# PTGSCH1.net
KiCad netlist of a schematic drawn in EAGLE
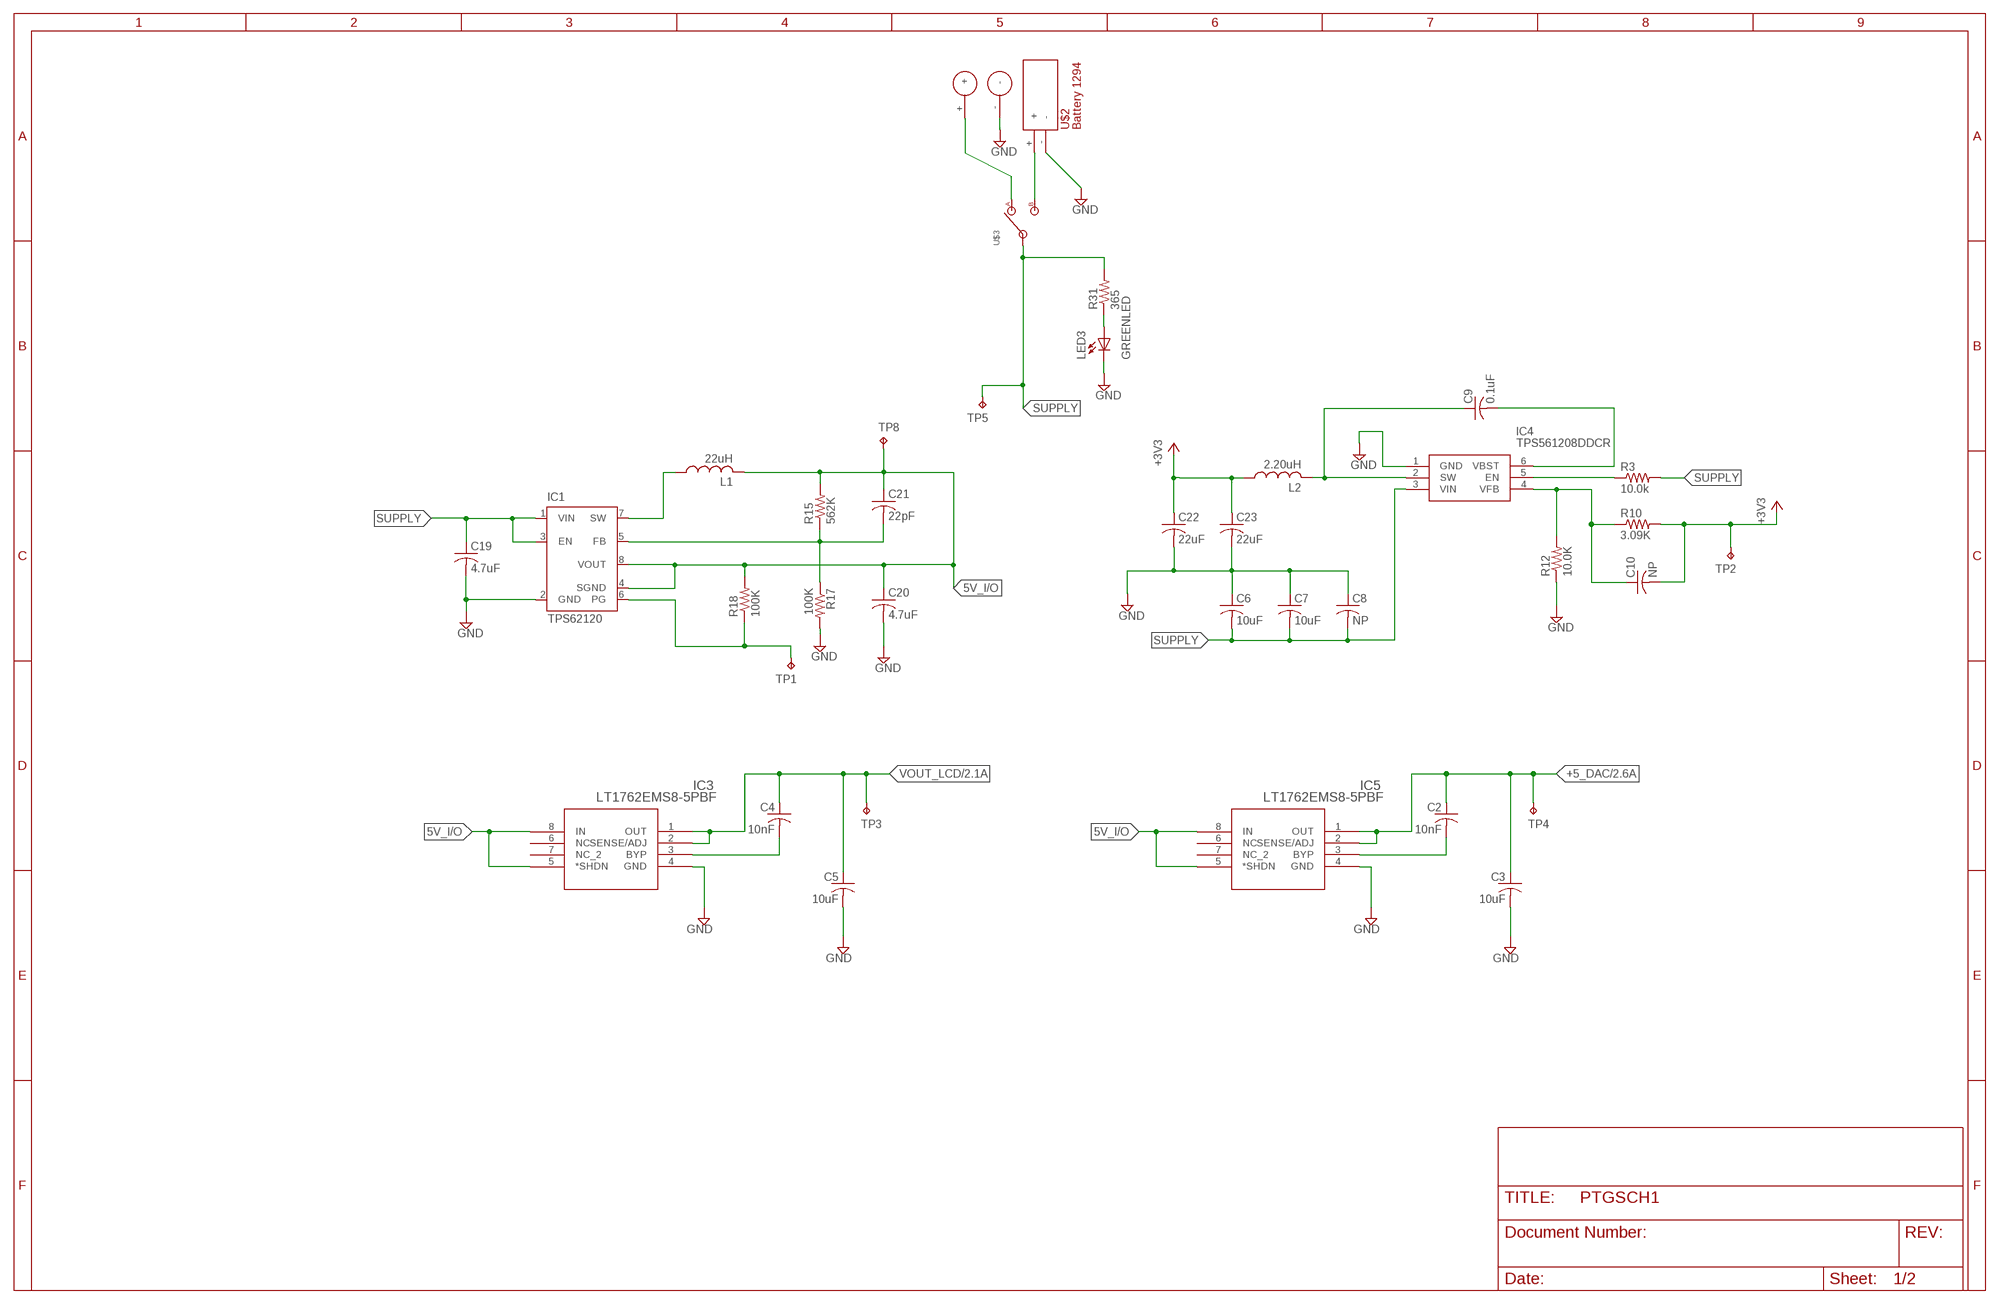
[diagram p0: schematic, sheet 1]
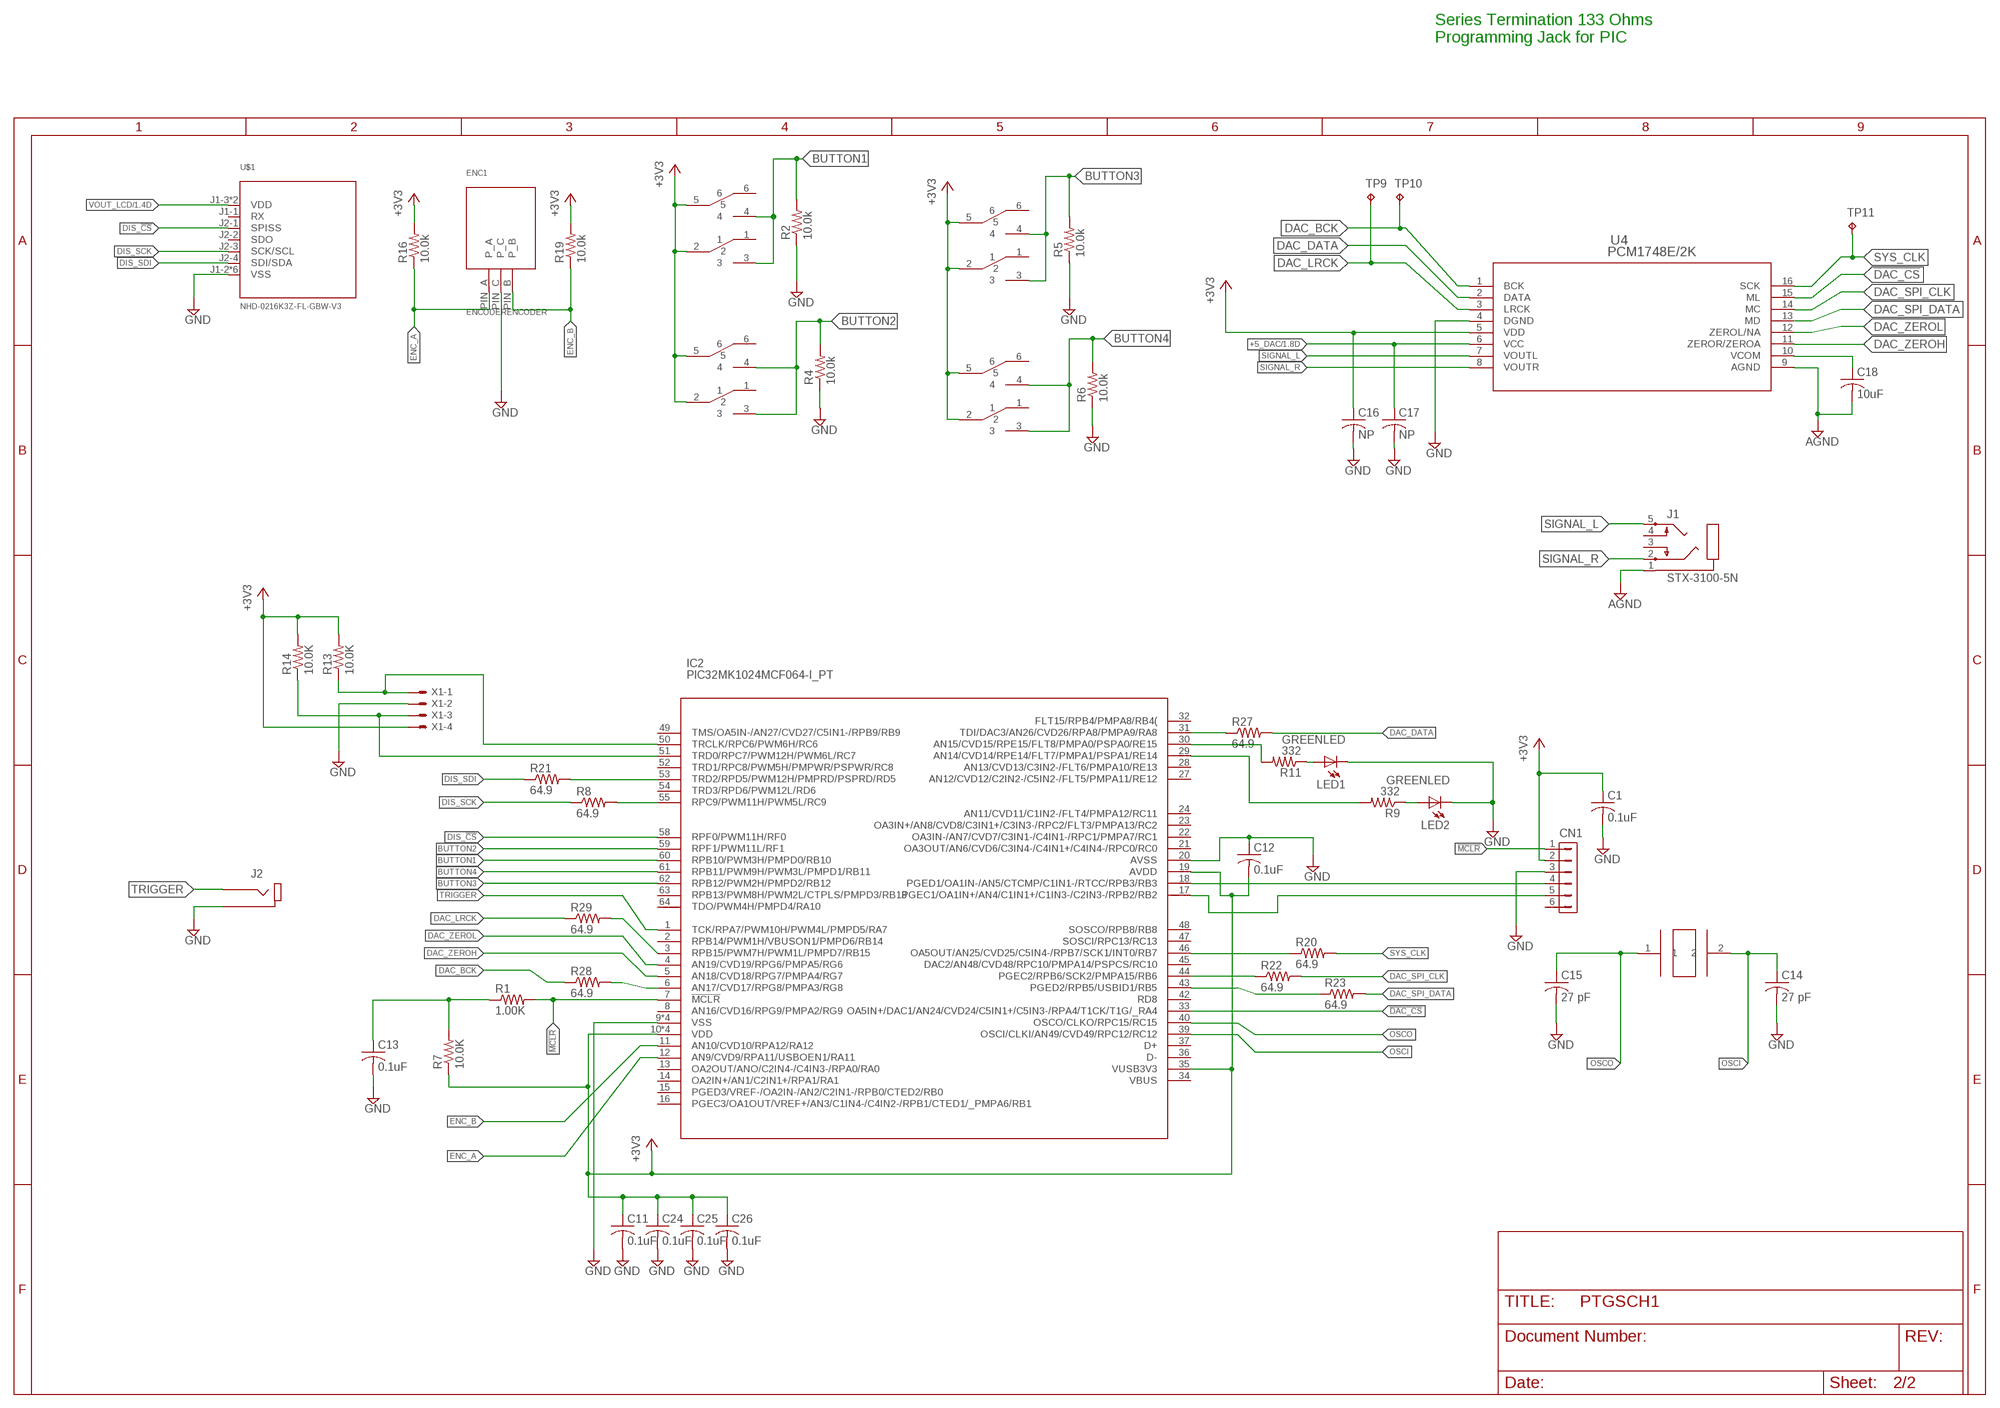
[diagram p1: schematic, sheet 2]

(export (version "E")
  (design (tool "Eeschema 10.0.6"))
  (components
    (comp (ref "C2")
      (value "10nF")
      (footprint "eagle-import:C0603")
      (libsource (lib "eagle-import") (part "C-USC0603"))
    )
    (comp (ref "C3")
      (value "10uF")
      (footprint "eagle-import:C0805")
      (libsource (lib "eagle-import") (part "C-USC0805"))
    )
    (comp (ref "C4")
      (value "10nF")
      (footprint "eagle-import:C0603")
      (libsource (lib "eagle-import") (part "C-USC0603"))
    )
    (comp (ref "C5")
      (value "10uF")
      (footprint "eagle-import:C0805")
      (libsource (lib "eagle-import") (part "C-USC0805"))
    )
    (comp (ref "C6")
      (value "10uF")
      (footprint "eagle-import:C0805")
      (libsource (lib "eagle-import") (part "C-USC0805"))
    )
    (comp (ref "C7")
      (value "10uF")
      (footprint "eagle-import:C0805")
      (libsource (lib "eagle-import") (part "C-USC0805"))
    )
    (comp (ref "C8")
      (value "NP")
      (footprint "eagle-import:C0805")
      (libsource (lib "eagle-import") (part "C-USC0805"))
    )
    (comp (ref "C9")
      (value "0.1uF")
      (footprint "eagle-import:C0805")
      (libsource (lib "eagle-import") (part "C-USC0805"))
    )
    (comp (ref "C10")
      (value "NP")
      (footprint "eagle-import:C0805")
      (libsource (lib "eagle-import") (part "C-USC0805"))
    )
    (comp (ref "C19")
      (value "4.7uF")
      (footprint "eagle-import:C0603")
      (libsource (lib "eagle-import") (part "C-USC0603"))
    )
    (comp (ref "C20")
      (value "4.7uF")
      (footprint "eagle-import:C0603")
      (libsource (lib "eagle-import") (part "C-USC0603"))
    )
    (comp (ref "C21")
      (value "22pF")
      (footprint "eagle-import:C0603")
      (libsource (lib "eagle-import") (part "C-USC0603"))
    )
    (comp (ref "C22")
      (value "22uF")
      (footprint "eagle-import:C0603")
      (libsource (lib "eagle-import") (part "C-USC0603"))
    )
    (comp (ref "C23")
      (value "22uF")
      (footprint "eagle-import:C0603")
      (libsource (lib "eagle-import") (part "C-USC0603"))
    )
    (comp (ref "IC1")
      (value "TPS62120")
      (footprint "eagle-import:DCN-R-PDSO-G8")
      (libsource (lib "eagle-import") (part "TPS62120"))
    )
    (comp (ref "IC3")
      (value "LT1762EMS8-5PBF")
      (footprint "eagle-import:MSOP-8_MS")
      (fields (field (name "MF") "Linear Technology") (field (name "MP") "LT1762EMS8-5#PBF"))
      (libsource (lib "eagle-import") (part "LT1762EMS8-5PBF"))
    )
    (comp (ref "IC4")
      (value "TPS561208DDCR")
      (footprint "eagle-import:SOT95P280X110-6N")
      (libsource (lib "eagle-import") (part "TPS561208DDCR"))
    )
    (comp (ref "IC5")
      (value "LT1762EMS8-5PBF")
      (footprint "eagle-import:MSOP-8_MS")
      (fields (field (name "MF") "Linear Technology") (field (name "MP") "LT1762EMS8-5#PBF"))
      (libsource (lib "eagle-import") (part "LT1762EMS8-5PBF"))
    )
    (comp (ref "L1")
      (value "22uH")
      (footprint "eagle-import:C0603K")
      (libsource (lib "eagle-import") (part "L-US0603"))
    )
    (comp (ref "L2")
      (value "2.20uH")
      (footprint "eagle-import:C0603K")
      (libsource (lib "eagle-import") (part "L-US0603"))
    )
    (comp (ref "LED3")
      (value "GREENLED")
      (footprint "eagle-import:0805_10MGAP")
      (libsource (lib "eagle-import") (part "GREENLED"))
    )
    (comp (ref "R3")
      (value "10.0k")
      (footprint "eagle-import:R0603")
      (libsource (lib "eagle-import") (part "resistor_R-US_R0603"))
    )
    (comp (ref "R10")
      (value "3.09K")
      (footprint "eagle-import:R0603")
      (libsource (lib "eagle-import") (part "resistor_R-US_R0603"))
    )
    (comp (ref "R12")
      (value "10.0K")
      (footprint "eagle-import:R0603")
      (libsource (lib "eagle-import") (part "resistor_R-US_R0603"))
    )
    (comp (ref "R15")
      (value "562K")
      (footprint "eagle-import:R0603")
      (libsource (lib "eagle-import") (part "resistor_R-US_R0603"))
    )
    (comp (ref "R17")
      (value "100K")
      (footprint "eagle-import:R0603")
      (libsource (lib "eagle-import") (part "resistor_R-US_R0603"))
    )
    (comp (ref "R18")
      (value "100K")
      (footprint "eagle-import:R0603")
      (libsource (lib "eagle-import") (part "resistor_R-US_R0603"))
    )
    (comp (ref "R31")
      (value "365")
      (footprint "eagle-import:R0603")
      (libsource (lib "eagle-import") (part "resistor_R-US_R0603"))
    )
    (comp (ref "TP1")
      (value "TPTP20SQ")
      (footprint "eagle-import:TP20SQ")
      (libsource (lib "eagle-import") (part "TPTP20SQ"))
    )
    (comp (ref "TP2")
      (value "TPTP20SQ")
      (footprint "eagle-import:TP20SQ")
      (libsource (lib "eagle-import") (part "TPTP20SQ"))
    )
    (comp (ref "TP3")
      (value "TPTP20SQ")
      (footprint "eagle-import:TP20SQ")
      (libsource (lib "eagle-import") (part "TPTP20SQ"))
    )
    (comp (ref "TP4")
      (value "TPTP20SQ")
      (footprint "eagle-import:TP20SQ")
      (libsource (lib "eagle-import") (part "TPTP20SQ"))
    )
    (comp (ref "TP5")
      (value "TPTP20SQ")
      (footprint "eagle-import:TP20SQ")
      (libsource (lib "eagle-import") (part "TPTP20SQ"))
    )
    (comp (ref "TP8")
      (value "TPTP20SQ")
      (footprint "eagle-import:TP20SQ")
      (libsource (lib "eagle-import") (part "TPTP20SQ"))
    )
    (comp (ref "U$2")
      (value "BATTERY_HOLDER")
      (footprint "eagle-import:HOLDER")
      (libsource (lib "eagle-import") (part "BATTERY_HOLDER"))
    )
    (comp (ref "U$3")
      (value "POWERSWITCH")
      (footprint "eagle-import:ROCKERVIAS")
      (libsource (lib "eagle-import") (part "POWERSWITCH"))
    )
    (comp (ref "U$4")
      (value "POWRPINS")
      (footprint "eagle-import:VOLTAGEPINS")
      (libsource (lib "eagle-import") (part "POWRPINS"))
    )
    (comp (ref "BUTTON1")
      (value "BUTTON-DPDT-7MM")
      (footprint "eagle-import:BUTTON-DPDT-7MM")
      (libsource (lib "eagle-import") (part "BUTTON-DPDT-7MM"))
    )
    (comp (ref "BUTTON2")
      (value "BUTTON-DPDT-7MM")
      (footprint "eagle-import:BUTTON-DPDT-7MM")
      (libsource (lib "eagle-import") (part "BUTTON-DPDT-7MM"))
    )
    (comp (ref "BUTTON3")
      (value "BUTTON-DPDT-7MM")
      (footprint "eagle-import:BUTTON-DPDT-7MM")
      (libsource (lib "eagle-import") (part "BUTTON-DPDT-7MM"))
    )
    (comp (ref "BUTTON4")
      (value "BUTTON-DPDT-7MM")
      (footprint "eagle-import:BUTTON-DPDT-7MM")
      (libsource (lib "eagle-import") (part "BUTTON-DPDT-7MM"))
    )
    (comp (ref "C1")
      (value "0.1uF")
      (footprint "eagle-import:C0805")
      (libsource (lib "eagle-import") (part "C-USC0805"))
    )
    (comp (ref "C11")
      (value "0.1uF")
      (footprint "eagle-import:C0805")
      (libsource (lib "eagle-import") (part "C-USC0805"))
    )
    (comp (ref "C12")
      (value "0.1uF")
      (footprint "eagle-import:C0805")
      (libsource (lib "eagle-import") (part "C-USC0805"))
    )
    (comp (ref "C13")
      (value "0.1uF")
      (footprint "eagle-import:C0805")
      (libsource (lib "eagle-import") (part "C-USC0805"))
    )
    (comp (ref "C14")
      (value "27 pF")
      (footprint "eagle-import:C0603")
      (libsource (lib "eagle-import") (part "C-USC0603"))
    )
    (comp (ref "C15")
      (value "27 pF")
      (footprint "eagle-import:C0603")
      (libsource (lib "eagle-import") (part "C-USC0603"))
    )
    (comp (ref "C16")
      (value "NP")
      (footprint "eagle-import:C0805")
      (libsource (lib "eagle-import") (part "C-USC0805"))
    )
    (comp (ref "C17")
      (value "NP")
      (footprint "eagle-import:C0805")
      (libsource (lib "eagle-import") (part "C-USC0805"))
    )
    (comp (ref "C18")
      (value "10uF")
      (footprint "eagle-import:C0805")
      (libsource (lib "eagle-import") (part "C-USC0805"))
    )
    (comp (ref "C24")
      (value "0.1uF")
      (footprint "eagle-import:C0805")
      (libsource (lib "eagle-import") (part "C-USC0805"))
    )
    (comp (ref "C25")
      (value "0.1uF")
      (footprint "eagle-import:C0805")
      (libsource (lib "eagle-import") (part "C-USC0805"))
    )
    (comp (ref "C26")
      (value "0.1uF")
      (footprint "eagle-import:C0805")
      (libsource (lib "eagle-import") (part "C-USC0805"))
    )
    (comp (ref "CN1")
      (value "HDR-1X6-SIP-100")
      (footprint "eagle-import:SIP-100-6V")
      (libsource (lib "eagle-import") (part "HDR-1X6-SIP-100"))
    )
    (comp (ref "ENC1")
      (value "ENCODERENCODER")
      (footprint "eagle-import:ENCODER")
      (libsource (lib "eagle-import") (part "ENCODERENCODER"))
    )
    (comp (ref "IC2")
      (value "PIC32MK1024MCF064-I_PT")
      (footprint "eagle-import:TQFP64-10X10")
      (libsource (lib "eagle-import") (part "PIC32MK1024MCF064-I_PT"))
    )
    (comp (ref "J1")
      (value "STX-3100-5N")
      (footprint "eagle-import:STX-3100-5N")
      (libsource (lib "eagle-import") (part "STX-3100-5N"))
    )
    (comp (ref "J2")
      (value "RCJ-01X_PHONO_SINGLE")
      (footprint "eagle-import:RCA_RA_PCB_SINGLE")
      (libsource (lib "eagle-import") (part "RCJ-01X_PHONO_SINGLE"))
    )
    (comp (ref "LED1")
      (value "GREENLED")
      (footprint "eagle-import:0805_10MGAP")
      (libsource (lib "eagle-import") (part "GREENLED"))
    )
    (comp (ref "LED2")
      (value "GREENLED")
      (footprint "eagle-import:0805_10MGAP")
      (libsource (lib "eagle-import") (part "GREENLED"))
    )
    (comp (ref "R1")
      (value "1.00K")
      (footprint "eagle-import:R0603")
      (libsource (lib "eagle-import") (part "resistor_R-US_R0603"))
    )
    (comp (ref "R2")
      (value "10.0k")
      (footprint "eagle-import:R0603")
      (libsource (lib "eagle-import") (part "R-US_R0603"))
    )
    (comp (ref "R4")
      (value "10.0k")
      (footprint "eagle-import:R0603")
      (libsource (lib "eagle-import") (part "R-US_R0603"))
    )
    (comp (ref "R5")
      (value "10.0k")
      (footprint "eagle-import:R0603")
      (libsource (lib "eagle-import") (part "R-US_R0603"))
    )
    (comp (ref "R6")
      (value "10.0k")
      (footprint "eagle-import:R0603")
      (libsource (lib "eagle-import") (part "R-US_R0603"))
    )
    (comp (ref "R7")
      (value "10.0K")
      (footprint "eagle-import:R0603")
      (libsource (lib "eagle-import") (part "resistor_R-US_R0603"))
    )
    (comp (ref "R8")
      (value "64.9")
      (footprint "eagle-import:R0603")
      (libsource (lib "eagle-import") (part "R-US_R0603"))
    )
    (comp (ref "R9")
      (value "332")
      (footprint "eagle-import:R0603")
      (libsource (lib "eagle-import") (part "R-US_R0603"))
    )
    (comp (ref "R11")
      (value "332")
      (footprint "eagle-import:R0603")
      (libsource (lib "eagle-import") (part "R-US_R0603"))
    )
    (comp (ref "R13")
      (value "10.0K")
      (footprint "eagle-import:R0603")
      (libsource (lib "eagle-import") (part "R-US_R0603"))
    )
    (comp (ref "R14")
      (value "10.0K")
      (footprint "eagle-import:R0603")
      (libsource (lib "eagle-import") (part "R-US_R0603"))
    )
    (comp (ref "R16")
      (value "10.0k")
      (footprint "eagle-import:R0603")
      (libsource (lib "eagle-import") (part "R-US_R0603"))
    )
    (comp (ref "R19")
      (value "10.0k")
      (footprint "eagle-import:R0603")
      (libsource (lib "eagle-import") (part "R-US_R0603"))
    )
    (comp (ref "R20")
      (value "64.9")
      (footprint "eagle-import:R0603")
      (libsource (lib "eagle-import") (part "R-US_R0603"))
    )
    (comp (ref "R21")
      (value "64.9")
      (footprint "eagle-import:R0603")
      (libsource (lib "eagle-import") (part "R-US_R0603"))
    )
    (comp (ref "R22")
      (value "64.9")
      (footprint "eagle-import:R0603")
      (libsource (lib "eagle-import") (part "R-US_R0603"))
    )
    (comp (ref "R23")
      (value "64.9")
      (footprint "eagle-import:R0603")
      (libsource (lib "eagle-import") (part "R-US_R0603"))
    )
    (comp (ref "R27")
      (value "64.9")
      (footprint "eagle-import:R0603")
      (libsource (lib "eagle-import") (part "R-US_R0603"))
    )
    (comp (ref "R28")
      (value "64.9")
      (footprint "eagle-import:R0603")
      (libsource (lib "eagle-import") (part "R-US_R0603"))
    )
    (comp (ref "R29")
      (value "64.9")
      (footprint "eagle-import:R0603")
      (libsource (lib "eagle-import") (part "R-US_R0603"))
    )
    (comp (ref "TP9")
      (value "TPTP20SQ")
      (footprint "eagle-import:TP20SQ")
      (libsource (lib "eagle-import") (part "TPTP20SQ"))
    )
    (comp (ref "TP10")
      (value "TPTP20SQ")
      (footprint "eagle-import:TP20SQ")
      (libsource (lib "eagle-import") (part "TPTP20SQ"))
    )
    (comp (ref "TP11")
      (value "TPTP20SQ")
      (footprint "eagle-import:TP20SQ")
      (libsource (lib "eagle-import") (part "TPTP20SQ"))
    )
    (comp (ref "U$1")
      (value "NHD-0216K3Z-FL-GBW-V3")
      (footprint "eagle-import:NHD-0216K3Z-FL-GBW-V3")
      (libsource (lib "eagle-import") (part "NHD-0216K3Z-FL-GBW-V3"))
    )
    (comp (ref "U$8")
      (value "EXTERNALCRYSTAL")
      (footprint "eagle-import:XTAL500X320X130N")
      (libsource (lib "eagle-import") (part "EXTERNALCRYSTAL"))
    )
    (comp (ref "U4")
      (value "PCM1748E/2K")
      (footprint "eagle-import:DBQ16")
      (fields (field (name "MANUFACTURER_PART_NUMBER") "PCM1748E2K"))
      (libsource (lib "eagle-import") (part "PCM1748E/2K"))
    )
    (comp (ref "X1")
      (value "22-23-2041")
      (footprint "eagle-import:22-23-2041")
      (fields (field (name "MF") "Molex"))
      (libsource (lib "eagle-import") (part "22-23-2041"))
    )
  )
  (nets
    (net (code "1") (name "+3V3") (class "Default")
      (node (ref "BUTTON1") (pin "2") (pinfunction "2_2") (pintype "bidirectional"))
      (node (ref "BUTTON1") (pin "5") (pinfunction "5_5") (pintype "bidirectional"))
      (node (ref "BUTTON2") (pin "2") (pinfunction "2_2") (pintype "bidirectional"))
      (node (ref "BUTTON2") (pin "5") (pinfunction "5_5") (pintype "bidirectional"))
      (node (ref "BUTTON3") (pin "2") (pinfunction "2_2") (pintype "bidirectional"))
      (node (ref "BUTTON3") (pin "5") (pinfunction "5_5") (pintype "bidirectional"))
      (node (ref "BUTTON4") (pin "2") (pinfunction "2_2") (pintype "bidirectional"))
      (node (ref "BUTTON4") (pin "5") (pinfunction "5_5") (pintype "bidirectional"))
      (node (ref "C1") (pin "1") (pinfunction "1_1") (pintype "passive"))
      (node (ref "C10") (pin "2") (pinfunction "2_2") (pintype "passive"))
      (node (ref "C11") (pin "1") (pinfunction "1_1") (pintype "passive"))
      (node (ref "C12") (pin "2") (pinfunction "2_2") (pintype "passive"))
      (node (ref "C16") (pin "1") (pinfunction "1_1") (pintype "passive"))
      (node (ref "C22") (pin "1") (pinfunction "1_1") (pintype "passive"))
      (node (ref "C23") (pin "1") (pinfunction "1_1") (pintype "passive"))
      (node (ref "C24") (pin "1") (pinfunction "1_1") (pintype "passive"))
      (node (ref "C25") (pin "1") (pinfunction "1_1") (pintype "passive"))
      (node (ref "C26") (pin "1") (pinfunction "1_1") (pintype "passive"))
      (node (ref "CN1") (pin "2") (pinfunction "2_2") (pintype "passive"))
      (node (ref "IC2") (pin "10") (pinfunction "VDD_10") (pintype "bidirectional"))
      (node (ref "IC2") (pin "19") (pinfunction "AVDD_19") (pintype "bidirectional"))
      (node (ref "IC2") (pin "26") (pinfunction "VDD_26") (pintype "bidirectional"))
      (node (ref "IC2") (pin "35") (pinfunction "VUSB3V3_35") (pintype "bidirectional"))
      (node (ref "IC2") (pin "38") (pinfunction "VDD_38") (pintype "bidirectional"))
      (node (ref "IC2") (pin "57") (pinfunction "VDD_57") (pintype "bidirectional"))
      (node (ref "L2") (pin "1") (pinfunction "1_1") (pintype "passive"))
      (node (ref "R10") (pin "2") (pinfunction "2_2") (pintype "passive"))
      (node (ref "R13") (pin "2") (pinfunction "2_2") (pintype "passive"))
      (node (ref "R14") (pin "2") (pinfunction "2_2") (pintype "passive"))
      (node (ref "R16") (pin "2") (pinfunction "2_2") (pintype "passive"))
      (node (ref "R19") (pin "2") (pinfunction "2_2") (pintype "passive"))
      (node (ref "R7") (pin "1") (pinfunction "1_1") (pintype "passive"))
      (node (ref "TP2") (pin "TP") (pinfunction "TP_TP") (pintype "input"))
      (node (ref "U4") (pin "5") (pinfunction "VDD_5") (pintype "power_in"))
      (node (ref "X1") (pin "4") (pinfunction "S_4") (pintype "passive"))
    )
    (net (code "2") (name "+5_DAC") (class "Default")
      (node (ref "C17") (pin "1") (pinfunction "1_1") (pintype "passive"))
      (node (ref "C2") (pin "1") (pinfunction "1_1") (pintype "passive"))
      (node (ref "C3") (pin "1") (pinfunction "1_1") (pintype "passive"))
      (node (ref "IC5") (pin "1") (pinfunction "OUT_1") (pintype "output"))
      (node (ref "IC5") (pin "2") (pinfunction "SENSE/ADJ_2") (pintype "bidirectional"))
      (node (ref "TP4") (pin "TP") (pinfunction "TP_TP") (pintype "input"))
      (node (ref "U4") (pin "6") (pinfunction "VCC_6") (pintype "power_in"))
    )
    (net (code "3") (name "5V_I{slash}O") (class "Default")
      (node (ref "C20") (pin "1") (pinfunction "1_1") (pintype "passive"))
      (node (ref "C21") (pin "1") (pinfunction "1_1") (pintype "passive"))
      (node (ref "IC1") (pin "4") (pinfunction "SGND_4") (pintype "passive"))
      (node (ref "IC1") (pin "8") (pinfunction "VOUT_8") (pintype "output"))
      (node (ref "IC3") (pin "5") (pinfunction "*SHDN_5") (pintype "output"))
      (node (ref "IC3") (pin "8") (pinfunction "IN_8") (pintype "input"))
      (node (ref "IC5") (pin "5") (pinfunction "*SHDN_5") (pintype "output"))
      (node (ref "IC5") (pin "8") (pinfunction "IN_8") (pintype "input"))
      (node (ref "L1") (pin "2") (pinfunction "2_2") (pintype "passive"))
      (node (ref "R15") (pin "2") (pinfunction "2_2") (pintype "passive"))
      (node (ref "R18") (pin "2") (pinfunction "2_2") (pintype "passive"))
      (node (ref "TP8") (pin "TP") (pinfunction "TP_TP") (pintype "input"))
    )
    (net (code "4") (name "AGND") (class "Default")
      (node (ref "C18") (pin "2") (pinfunction "2_2") (pintype "passive"))
      (node (ref "J1") (pin "1") (pinfunction "1_1") (pintype "passive"))
      (node (ref "U4") (pin "9") (pinfunction "AGND_9") (pintype "power_in"))
    )
    (net (code "5") (name "BUTTON1") (class "Default")
      (node (ref "BUTTON1") (pin "3") (pinfunction "3_3") (pintype "bidirectional"))
      (node (ref "BUTTON1") (pin "4") (pinfunction "4_4") (pintype "bidirectional"))
      (node (ref "IC2") (pin "60") (pinfunction "RPB10/PWM3H/PMPD0/RB10_60") (pintype "bidirectional"))
      (node (ref "R2") (pin "2") (pinfunction "2_2") (pintype "passive"))
    )
    (net (code "6") (name "BUTTON2") (class "Default")
      (node (ref "BUTTON2") (pin "3") (pinfunction "3_3") (pintype "bidirectional"))
      (node (ref "BUTTON2") (pin "4") (pinfunction "4_4") (pintype "bidirectional"))
      (node (ref "IC2") (pin "59") (pinfunction "RPF1/PWM11L/RF1_59") (pintype "bidirectional"))
      (node (ref "R4") (pin "2") (pinfunction "2_2") (pintype "passive"))
    )
    (net (code "7") (name "BUTTON3") (class "Default")
      (node (ref "BUTTON3") (pin "3") (pinfunction "3_3") (pintype "bidirectional"))
      (node (ref "BUTTON3") (pin "4") (pinfunction "4_4") (pintype "bidirectional"))
      (node (ref "IC2") (pin "62") (pinfunction "RPB12/PWM2H/PMPD2/RB12_62") (pintype "bidirectional"))
      (node (ref "R5") (pin "2") (pinfunction "2_2") (pintype "passive"))
    )
    (net (code "8") (name "BUTTON4") (class "Default")
      (node (ref "BUTTON4") (pin "3") (pinfunction "3_3") (pintype "bidirectional"))
      (node (ref "BUTTON4") (pin "4") (pinfunction "4_4") (pintype "bidirectional"))
      (node (ref "IC2") (pin "61") (pinfunction "RPB11/PWM9H/PWM3L/PMPD1/RB11_61") (pintype "bidirectional"))
      (node (ref "R6") (pin "2") (pinfunction "2_2") (pintype "passive"))
    )
    (net (code "9") (name "DAC_BCK") (class "Default")
      (node (ref "R28") (pin "1") (pinfunction "1_1") (pintype "passive"))
      (node (ref "TP10") (pin "TP") (pinfunction "TP_TP") (pintype "input"))
      (node (ref "U4") (pin "1") (pinfunction "BCK_1") (pintype "input"))
    )
    (net (code "10") (name "DAC_DATA") (class "Default")
      (node (ref "R27") (pin "2") (pinfunction "2_2") (pintype "passive"))
      (node (ref "U4") (pin "2") (pinfunction "DATA_2") (pintype "input"))
    )
    (net (code "11") (name "DAC_LRCK") (class "Default")
      (node (ref "R29") (pin "1") (pinfunction "1_1") (pintype "passive"))
      (node (ref "TP9") (pin "TP") (pinfunction "TP_TP") (pintype "input"))
      (node (ref "U4") (pin "3") (pinfunction "LRCK_3") (pintype "input"))
    )
    (net (code "12") (name "DAC_SPI_CLK") (class "Default")
      (node (ref "R22") (pin "2") (pinfunction "2_2") (pintype "passive"))
      (node (ref "U4") (pin "14") (pinfunction "MC_14") (pintype "input"))
    )
    (net (code "13") (name "DAC_SPI_DATA") (class "Default")
      (node (ref "R23") (pin "2") (pinfunction "2_2") (pintype "passive"))
      (node (ref "U4") (pin "13") (pinfunction "MD_13") (pintype "input"))
    )
    (net (code "14") (name "DAC_ZEROH") (class "Default")
      (node (ref "IC2") (pin "5") (pinfunction "AN18/CVD18/RPG7/PMPA4/RG7_5") (pintype "bidirectional"))
      (node (ref "U4") (pin "11") (pinfunction "ZEROR/ZEROA_11") (pintype "output"))
    )
    (net (code "15") (name "DAC_ZEROL") (class "Default")
      (node (ref "IC2") (pin "4") (pinfunction "AN19/CVD19/RPG6/PMPA5/RG6_4") (pintype "bidirectional"))
      (node (ref "U4") (pin "12") (pinfunction "ZEROL/NA_12") (pintype "output"))
    )
    (net (code "16") (name "DIS_SCK") (class "Default")
      (node (ref "R8") (pin "1") (pinfunction "1_1") (pintype "passive"))
      (node (ref "U$1") (pin "J2-3") (pinfunction "SCK/SCL_J2-3") (pintype "bidirectional"))
    )
    (net (code "17") (name "DIS_SDI") (class "Default")
      (node (ref "R21") (pin "1") (pinfunction "1_1") (pintype "passive"))
      (node (ref "U$1") (pin "J2-4") (pinfunction "SDI/SDA_J2-4") (pintype "bidirectional"))
    )
    (net (code "18") (name "DIS_~{CS}") (class "Default")
      (node (ref "IC2") (pin "58") (pinfunction "RPF0/PWM11H/RF0_58") (pintype "bidirectional"))
      (node (ref "U$1") (pin "J2-1") (pinfunction "SPISS_J2-1") (pintype "bidirectional"))
    )
    (net (code "19") (name "ENC_A") (class "Default")
      (node (ref "ENC1") (pin "PIN_A") (pinfunction "P_A_PIN_A") (pintype "bidirectional"))
      (node (ref "IC2") (pin "12") (pinfunction "AN9/CVD9/RPA11/USBOEN1/RA11_12") (pintype "bidirectional"))
      (node (ref "R16") (pin "1") (pinfunction "1_1") (pintype "passive"))
    )
    (net (code "20") (name "ENC_B") (class "Default")
      (node (ref "ENC1") (pin "PIN_B") (pinfunction "P_B_PIN_B") (pintype "bidirectional"))
      (node (ref "IC2") (pin "11") (pinfunction "AN10/CVD10/RPA12/RA12_11") (pintype "bidirectional"))
      (node (ref "R19") (pin "1") (pinfunction "1_1") (pintype "passive"))
    )
    (net (code "21") (name "GND") (class "Default")
      (node (ref "C1") (pin "2") (pinfunction "2_2") (pintype "passive"))
      (node (ref "C11") (pin "2") (pinfunction "2_2") (pintype "passive"))
      (node (ref "C12") (pin "1") (pinfunction "1_1") (pintype "passive"))
      (node (ref "C13") (pin "2") (pinfunction "2_2") (pintype "passive"))
      (node (ref "C14") (pin "2") (pinfunction "2_2") (pintype "passive"))
      (node (ref "C15") (pin "2") (pinfunction "2_2") (pintype "passive"))
      (node (ref "C16") (pin "2") (pinfunction "2_2") (pintype "passive"))
      (node (ref "C17") (pin "2") (pinfunction "2_2") (pintype "passive"))
      (node (ref "C19") (pin "2") (pinfunction "2_2") (pintype "passive"))
      (node (ref "C20") (pin "2") (pinfunction "2_2") (pintype "passive"))
      (node (ref "C22") (pin "2") (pinfunction "2_2") (pintype "passive"))
      (node (ref "C23") (pin "2") (pinfunction "2_2") (pintype "passive"))
      (node (ref "C24") (pin "2") (pinfunction "2_2") (pintype "passive"))
      (node (ref "C25") (pin "2") (pinfunction "2_2") (pintype "passive"))
      (node (ref "C26") (pin "2") (pinfunction "2_2") (pintype "passive"))
      (node (ref "C3") (pin "2") (pinfunction "2_2") (pintype "passive"))
      (node (ref "C5") (pin "2") (pinfunction "2_2") (pintype "passive"))
      (node (ref "C6") (pin "1") (pinfunction "1_1") (pintype "passive"))
      (node (ref "C7") (pin "1") (pinfunction "1_1") (pintype "passive"))
      (node (ref "C8") (pin "1") (pinfunction "1_1") (pintype "passive"))
      (node (ref "CN1") (pin "3") (pinfunction "3_3") (pintype "passive"))
      (node (ref "ENC1") (pin "PIN_C") (pinfunction "P_C_PIN_C") (pintype "bidirectional"))
      (node (ref "IC1") (pin "2") (pinfunction "GND_2") (pintype "power_in"))
      (node (ref "IC2") (pin "20") (pinfunction "AVSS_20") (pintype "bidirectional"))
      (node (ref "IC2") (pin "25") (pinfunction "VSS_25") (pintype "bidirectional"))
      (node (ref "IC2") (pin "41") (pinfunction "VSS_41") (pintype "bidirectional"))
      (node (ref "IC2") (pin "56") (pinfunction "VSS_56") (pintype "bidirectional"))
      (node (ref "IC2") (pin "9") (pinfunction "VSS_9") (pintype "bidirectional"))
      (node (ref "IC3") (pin "4") (pinfunction "GND_4") (pintype "power_in"))
      (node (ref "IC4") (pin "1") (pinfunction "GND_1") (pintype "bidirectional"))
      (node (ref "IC5") (pin "4") (pinfunction "GND_4") (pintype "power_in"))
      (node (ref "J2") (pin "1") (pinfunction "SH_1") (pintype "passive"))
      (node (ref "LED1") (pin "1") (pinfunction "-_1") (pintype "passive"))
      (node (ref "LED2") (pin "1") (pinfunction "-_1") (pintype "passive"))
      (node (ref "LED3") (pin "1") (pinfunction "-_1") (pintype "passive"))
      (node (ref "R12") (pin "1") (pinfunction "1_1") (pintype "passive"))
      (node (ref "R17") (pin "2") (pinfunction "2_2") (pintype "passive"))
      (node (ref "R2") (pin "1") (pinfunction "1_1") (pintype "passive"))
      (node (ref "R4") (pin "1") (pinfunction "1_1") (pintype "passive"))
      (node (ref "R5") (pin "1") (pinfunction "1_1") (pintype "passive"))
      (node (ref "R6") (pin "1") (pinfunction "1_1") (pintype "passive"))
      (node (ref "U$1") (pin "J1-2") (pinfunction "VSS_J1-2") (pintype "bidirectional"))
      (node (ref "U$1") (pin "J2-5") (pinfunction "VSS_J2-5") (pintype "bidirectional"))
      (node (ref "U$1") (pin "M1") (pinfunction "VSS_M1") (pintype "bidirectional"))
      (node (ref "U$1") (pin "M2") (pinfunction "VSS_M2") (pintype "bidirectional"))
      (node (ref "U$1") (pin "M3") (pinfunction "VSS_M3") (pintype "bidirectional"))
      (node (ref "U$1") (pin "M4") (pinfunction "VSS_M4") (pintype "bidirectional"))
      (node (ref "U$2") (pin "-") (pinfunction "-_-") (pintype "bidirectional"))
      (node (ref "U$4") (pin "-") (pinfunction "-_-") (pintype "bidirectional"))
      (node (ref "U4") (pin "4") (pinfunction "DGND_4") (pintype "power_in"))
      (node (ref "X1") (pin "2") (pinfunction "S_2") (pintype "passive"))
    )
    (net (code "22") (name "Net-(C13-Pad1)") (class "Default")
      (node (ref "C13") (pin "1") (pinfunction "1_1") (pintype "passive"))
      (node (ref "R1") (pin "1") (pinfunction "1_1") (pintype "passive"))
      (node (ref "R7") (pin "2") (pinfunction "2_2") (pintype "passive"))
    )
    (net (code "23") (name "Net-(IC1-FB)") (class "Default")
      (node (ref "C21") (pin "2") (pinfunction "2_2") (pintype "passive"))
      (node (ref "IC1") (pin "5") (pinfunction "FB_5") (pintype "input"))
      (node (ref "R15") (pin "1") (pinfunction "1_1") (pintype "passive"))
      (node (ref "R17") (pin "1") (pinfunction "1_1") (pintype "passive"))
    )
    (net (code "24") (name "Net-(IC1-PG)") (class "Default")
      (node (ref "IC1") (pin "6") (pinfunction "PG_6") (pintype "passive"))
      (node (ref "R18") (pin "1") (pinfunction "1_1") (pintype "passive"))
      (node (ref "TP1") (pin "TP") (pinfunction "TP_TP") (pintype "input"))
    )
    (net (code "25") (name "Net-(IC1-SW)") (class "Default")
      (node (ref "IC1") (pin "7") (pinfunction "SW_7") (pintype "output"))
      (node (ref "L1") (pin "1") (pinfunction "1_1") (pintype "passive"))
    )
    (net (code "26") (name "Net-(IC2-AN14{slash}CVD14{slash}RPE14{slash}FLT7{slash}PMPA1{slash}PSPA1{slash}RE14)") (class "Default")
      (node (ref "IC2") (pin "29") (pinfunction "AN14/CVD14/RPE14/FLT7/PMPA1/PSPA1/RE14_29") (pintype "bidirectional"))
      (node (ref "R9") (pin "2") (pinfunction "2_2") (pintype "passive"))
    )
    (net (code "27") (name "Net-(IC2-AN15{slash}CVD15{slash}RPE15{slash}FLT8{slash}PMPA0{slash}PSPA0{slash}RE15)") (class "Default")
      (node (ref "IC2") (pin "30") (pinfunction "AN15/CVD15/RPE15/FLT8/PMPA0/PSPA0/RE15_30") (pintype "bidirectional"))
      (node (ref "R11") (pin "2") (pinfunction "2_2") (pintype "passive"))
    )
    (net (code "28") (name "Net-(IC2-AN17{slash}CVD17{slash}RPG8{slash}PMPA3{slash}RG8)") (class "Default")
      (node (ref "IC2") (pin "6") (pinfunction "AN17/CVD17/RPG8/PMPA3/RG8_6") (pintype "bidirectional"))
      (node (ref "R28") (pin "2") (pinfunction "2_2") (pintype "passive"))
    )
    (net (code "29") (name "Net-(IC2-OA5OUT{slash}AN25{slash}CVD25{slash}C5IN4-{slash}RPB7{slash}SCK1{slash}INT0{slash}RB7)") (class "Default")
      (node (ref "IC2") (pin "46") (pinfunction "OA5OUT/AN25/CVD25/C5IN4-/RPB7/SCK1/INT0/RB7_46") (pintype "bidirectional"))
      (node (ref "R20") (pin "1") (pinfunction "1_1") (pintype "passive"))
    )
    (net (code "30") (name "Net-(IC2-PGEC1{slash}OA1IN+{slash}AN4{slash}C1IN1+{slash}C1IN3-{slash}C2IN3-{slash}RPB2{slash}RB2)") (class "Default")
      (node (ref "CN1") (pin "5") (pinfunction "5_5") (pintype "passive"))
      (node (ref "IC2") (pin "17") (pinfunction "PGEC1/OA1IN+/AN4/C1IN1+/C1IN3-/C2IN3-/RPB2/RB2_17") (pintype "bidirectional"))
    )
    (net (code "31") (name "Net-(IC2-PGEC2{slash}RPB6{slash}SCK2{slash}PMPA15{slash}RB6)") (class "Default")
      (node (ref "IC2") (pin "44") (pinfunction "PGEC2/RPB6/SCK2/PMPA15/RB6_44") (pintype "bidirectional"))
      (node (ref "R22") (pin "1") (pinfunction "1_1") (pintype "passive"))
    )
    (net (code "32") (name "Net-(IC2-PGED1{slash}OA1IN-{slash}AN5{slash}CTCMP{slash}C1IN1-{slash}RTCC{slash}RPB3{slash}RB3)") (class "Default")
      (node (ref "CN1") (pin "4") (pinfunction "4_4") (pintype "passive"))
      (node (ref "IC2") (pin "18") (pinfunction "PGED1/OA1IN-/AN5/CTCMP/C1IN1-/RTCC/RPB3/RB3_18") (pintype "bidirectional"))
    )
    (net (code "33") (name "Net-(IC2-PGED2{slash}RPB5{slash}USBID1{slash}RB5)") (class "Default")
      (node (ref "IC2") (pin "43") (pinfunction "PGED2/RPB5/USBID1/RB5_43") (pintype "bidirectional"))
      (node (ref "R23") (pin "1") (pinfunction "1_1") (pintype "passive"))
    )
    (net (code "34") (name "Net-(IC2-RPB15{slash}PWM7H{slash}PWM1L{slash}PMPD7{slash}RB15)") (class "Default")
      (node (ref "IC2") (pin "3") (pinfunction "RPB15/PWM7H/PWM1L/PMPD7/RB15_3") (pintype "bidirectional"))
      (node (ref "R29") (pin "2") (pinfunction "2_2") (pintype "passive"))
    )
    (net (code "35") (name "Net-(IC2-RPC9{slash}PWM11H{slash}PWM5L{slash}RC9)") (class "Default")
      (node (ref "IC2") (pin "55") (pinfunction "RPC9/PWM11H/PWM5L/RC9_55") (pintype "bidirectional"))
      (node (ref "R8") (pin "2") (pinfunction "2_2") (pintype "passive"))
    )
    (net (code "36") (name "Net-(IC2-TDI{slash}DAC3{slash}AN26{slash}CVD26{slash}RPA8{slash}PMPA9{slash}RA8)") (class "Default")
      (node (ref "IC2") (pin "31") (pinfunction "TDI/DAC3/AN26/CVD26/RPA8/PMPA9/RA8_31") (pintype "bidirectional"))
      (node (ref "R27") (pin "1") (pinfunction "1_1") (pintype "passive"))
    )
    (net (code "37") (name "Net-(IC2-TRCLK{slash}RPC6{slash}PWM6H{slash}RC6)") (class "Default")
      (node (ref "IC2") (pin "50") (pinfunction "TRCLK/RPC6/PWM6H/RC6_50") (pintype "bidirectional"))
      (node (ref "R13") (pin "1") (pinfunction "1_1") (pintype "passive"))
      (node (ref "X1") (pin "1") (pinfunction "S_1") (pintype "passive"))
    )
    (net (code "38") (name "Net-(IC2-TRD0{slash}RPC7{slash}PWM12H{slash}PWM6L{slash}RC7)") (class "Default")
      (node (ref "IC2") (pin "51") (pinfunction "TRD0/RPC7/PWM12H/PWM6L/RC7_51") (pintype "bidirectional"))
      (node (ref "R14") (pin "1") (pinfunction "1_1") (pintype "passive"))
      (node (ref "X1") (pin "3") (pinfunction "S_3") (pintype "passive"))
    )
    (net (code "39") (name "Net-(IC2-TRD2{slash}RPD5{slash}PWM12H{slash}PMPRD{slash}PSPRD{slash}RD5)") (class "Default")
      (node (ref "IC2") (pin "53") (pinfunction "TRD2/RPD5/PWM12H/PMPRD/PSPRD/RD5_53") (pintype "bidirectional"))
      (node (ref "R21") (pin "2") (pinfunction "2_2") (pintype "passive"))
    )
    (net (code "40") (name "Net-(IC3-BYP)") (class "Default")
      (node (ref "C4") (pin "2") (pinfunction "2_2") (pintype "passive"))
      (node (ref "IC3") (pin "3") (pinfunction "BYP_3") (pintype "output"))
    )
    (net (code "41") (name "Net-(IC4-EN)") (class "Default")
      (node (ref "IC4") (pin "5") (pinfunction "EN_5") (pintype "bidirectional"))
      (node (ref "R3") (pin "1") (pinfunction "1_1") (pintype "passive"))
    )
    (net (code "42") (name "Net-(IC4-SW)") (class "Default")
      (node (ref "C9") (pin "1") (pinfunction "1_1") (pintype "passive"))
      (node (ref "IC4") (pin "2") (pinfunction "SW_2") (pintype "bidirectional"))
      (node (ref "L2") (pin "2") (pinfunction "2_2") (pintype "passive"))
    )
    (net (code "43") (name "Net-(IC4-VBST)") (class "Default")
      (node (ref "C9") (pin "2") (pinfunction "2_2") (pintype "passive"))
      (node (ref "IC4") (pin "6") (pinfunction "VBST_6") (pintype "bidirectional"))
    )
    (net (code "44") (name "Net-(IC4-VFB)") (class "Default")
      (node (ref "C10") (pin "1") (pinfunction "1_1") (pintype "passive"))
      (node (ref "IC4") (pin "4") (pinfunction "VFB_4") (pintype "bidirectional"))
      (node (ref "R10") (pin "1") (pinfunction "1_1") (pintype "passive"))
      (node (ref "R12") (pin "2") (pinfunction "2_2") (pintype "passive"))
    )
    (net (code "45") (name "Net-(IC5-BYP)") (class "Default")
      (node (ref "C2") (pin "2") (pinfunction "2_2") (pintype "passive"))
      (node (ref "IC5") (pin "3") (pinfunction "BYP_3") (pintype "output"))
    )
    (net (code "46") (name "Net-(LED1-+)") (class "Default")
      (node (ref "LED1") (pin "2") (pinfunction "+_2") (pintype "passive"))
      (node (ref "R11") (pin "1") (pinfunction "1_1") (pintype "passive"))
    )
    (net (code "47") (name "Net-(LED2-+)") (class "Default")
      (node (ref "LED2") (pin "2") (pinfunction "+_2") (pintype "passive"))
      (node (ref "R9") (pin "1") (pinfunction "1_1") (pintype "passive"))
    )
    (net (code "48") (name "Net-(LED3-+)") (class "Default")
      (node (ref "LED3") (pin "2") (pinfunction "+_2") (pintype "passive"))
      (node (ref "R31") (pin "1") (pinfunction "1_1") (pintype "passive"))
    )
    (net (code "49") (name "Net-(U$2-Pad+)") (class "Default")
      (node (ref "U$2") (pin "+") (pinfunction "+_+") (pintype "bidirectional"))
      (node (ref "U$3") (pin "3") (pinfunction "3_3") (pintype "bidirectional"))
    )
    (net (code "50") (name "Net-(U$3-Pad1)") (class "Default")
      (node (ref "U$3") (pin "1") (pinfunction "1_1") (pintype "bidirectional"))
      (node (ref "U$4") (pin "+") (pinfunction "+_+") (pintype "bidirectional"))
    )
    (net (code "51") (name "Net-(U4-VCOM)") (class "Default")
      (node (ref "C18") (pin "1") (pinfunction "1_1") (pintype "passive"))
      (node (ref "U4") (pin "10") (pinfunction "VCOM_10") (pintype "power_in"))
    )
    (net (code "52") (name "OSCI") (class "Default")
      (node (ref "C14") (pin "1") (pinfunction "1_1") (pintype "passive"))
      (node (ref "IC2") (pin "39") (pinfunction "OSCI/CLKI/AN49/CVD49/RPC12/RC12_39") (pintype "bidirectional"))
      (node (ref "U$8") (pin "2") (pinfunction "2_2") (pintype "bidirectional"))
    )
    (net (code "53") (name "OSCO") (class "Default")
      (node (ref "C15") (pin "1") (pinfunction "1_1") (pintype "passive"))
      (node (ref "IC2") (pin "40") (pinfunction "OSCO/CLKO/RPC15/RC15_40") (pintype "bidirectional"))
      (node (ref "U$8") (pin "1") (pinfunction "1_1") (pintype "bidirectional"))
    )
    (net (code "54") (name "SIGNAL_L") (class "Default")
      (node (ref "J1") (pin "5") (pinfunction "5_5") (pintype "passive"))
      (node (ref "U4") (pin "7") (pinfunction "VOUTL_7") (pintype "output"))
    )
    (net (code "55") (name "SIGNAL_R") (class "Default")
      (node (ref "J1") (pin "2") (pinfunction "2_2") (pintype "passive"))
      (node (ref "U4") (pin "8") (pinfunction "VOUTR_8") (pintype "output"))
    )
    (net (code "56") (name "SUPPLY") (class "Default")
      (node (ref "C19") (pin "1") (pinfunction "1_1") (pintype "passive"))
      (node (ref "C6") (pin "2") (pinfunction "2_2") (pintype "passive"))
      (node (ref "C7") (pin "2") (pinfunction "2_2") (pintype "passive"))
      (node (ref "C8") (pin "2") (pinfunction "2_2") (pintype "passive"))
      (node (ref "IC1") (pin "1") (pinfunction "VIN_1") (pintype "input"))
      (node (ref "IC1") (pin "3") (pinfunction "EN_3") (pintype "input"))
      (node (ref "IC4") (pin "3") (pinfunction "VIN_3") (pintype "bidirectional"))
      (node (ref "R3") (pin "2") (pinfunction "2_2") (pintype "passive"))
      (node (ref "R31") (pin "2") (pinfunction "2_2") (pintype "passive"))
      (node (ref "TP5") (pin "TP") (pinfunction "TP_TP") (pintype "input"))
      (node (ref "U$3") (pin "2") (pinfunction "2_2") (pintype "bidirectional"))
    )
    (net (code "57") (name "SYS_CLK") (class "Default")
      (node (ref "R20") (pin "2") (pinfunction "2_2") (pintype "passive"))
      (node (ref "TP11") (pin "TP") (pinfunction "TP_TP") (pintype "input"))
      (node (ref "U4") (pin "16") (pinfunction "SCK_16") (pintype "input"))
    )
    (net (code "58") (name "TRIGGER") (class "Default")
      (node (ref "IC2") (pin "1") (pinfunction "TCK/RPA7/PWM10H/PWM4L/PMPD5/RA7_1") (pintype "bidirectional"))
      (node (ref "J2") (pin "2") (pinfunction "PIN_2") (pintype "passive"))
    )
    (net (code "59") (name "VOUT_LCD") (class "Default")
      (node (ref "C4") (pin "1") (pinfunction "1_1") (pintype "passive"))
      (node (ref "C5") (pin "1") (pinfunction "1_1") (pintype "passive"))
      (node (ref "IC3") (pin "1") (pinfunction "OUT_1") (pintype "output"))
      (node (ref "IC3") (pin "2") (pinfunction "SENSE/ADJ_2") (pintype "bidirectional"))
      (node (ref "TP3") (pin "TP") (pinfunction "TP_TP") (pintype "input"))
      (node (ref "U$1") (pin "J1-3") (pinfunction "VDD_J1-3") (pintype "bidirectional"))
      (node (ref "U$1") (pin "J2-6") (pinfunction "VDD_J2-6") (pintype "bidirectional"))
    )
    (net (code "60") (name "unconnected-(BUTTON1-Pad1)") (class "Default")
      (node (ref "BUTTON1") (pin "1") (pinfunction "1_1") (pintype "bidirectional"))
    )
    (net (code "61") (name "unconnected-(BUTTON1-Pad6)") (class "Default")
      (node (ref "BUTTON1") (pin "6") (pinfunction "6_6") (pintype "bidirectional"))
    )
    (net (code "62") (name "unconnected-(BUTTON2-Pad1)") (class "Default")
      (node (ref "BUTTON2") (pin "1") (pinfunction "1_1") (pintype "bidirectional"))
    )
    (net (code "63") (name "unconnected-(BUTTON2-Pad6)") (class "Default")
      (node (ref "BUTTON2") (pin "6") (pinfunction "6_6") (pintype "bidirectional"))
    )
    (net (code "64") (name "unconnected-(BUTTON3-Pad1)") (class "Default")
      (node (ref "BUTTON3") (pin "1") (pinfunction "1_1") (pintype "bidirectional"))
    )
    (net (code "65") (name "unconnected-(BUTTON3-Pad6)") (class "Default")
      (node (ref "BUTTON3") (pin "6") (pinfunction "6_6") (pintype "bidirectional"))
    )
    (net (code "66") (name "unconnected-(BUTTON4-Pad1)") (class "Default")
      (node (ref "BUTTON4") (pin "1") (pinfunction "1_1") (pintype "bidirectional"))
    )
    (net (code "67") (name "unconnected-(BUTTON4-Pad6)") (class "Default")
      (node (ref "BUTTON4") (pin "6") (pinfunction "6_6") (pintype "bidirectional"))
    )
    (net (code "68") (name "unconnected-(CN1-Pad6)") (class "Default")
      (node (ref "CN1") (pin "6") (pinfunction "6_6") (pintype "passive"))
    )
    (net (code "69") (name "unconnected-(IC2-AN11{slash}CVD11{slash}C1IN2-{slash}FLT4{slash}PMPA12{slash}RC11-Pad24)") (class "Default")
      (node (ref "IC2") (pin "24") (pinfunction "AN11/CVD11/C1IN2-/FLT4/PMPA12/RC11_24") (pintype "bidirectional"))
    )
    (net (code "70") (name "unconnected-(IC2-AN12{slash}CVD12{slash}C2IN2-{slash}C5IN2-{slash}FLT5{slash}PMPA11{slash}RE12-Pad27)") (class "Default")
      (node (ref "IC2") (pin "27") (pinfunction "AN12/CVD12/C2IN2-/C5IN2-/FLT5/PMPA11/RE12_27") (pintype "bidirectional"))
    )
    (net (code "71") (name "unconnected-(IC2-AN13{slash}CVD13{slash}C3IN2-{slash}FLT6{slash}PMPA10{slash}RE13-Pad28)") (class "Default")
      (node (ref "IC2") (pin "28") (pinfunction "AN13/CVD13/C3IN2-/FLT6/PMPA10/RE13_28") (pintype "bidirectional"))
    )
    (net (code "72") (name "unconnected-(IC2-AN16{slash}CVD16{slash}RPG9{slash}PMPA2{slash}RG9-Pad8)") (class "Default")
      (node (ref "IC2") (pin "8") (pinfunction "AN16/CVD16/RPG9/PMPA2/RG9_8") (pintype "bidirectional"))
    )
    (net (code "73") (name "unconnected-(IC2-D+-Pad37)") (class "Default")
      (node (ref "IC2") (pin "37") (pinfunction "D+_37") (pintype "bidirectional"))
    )
    (net (code "74") (name "unconnected-(IC2-D--Pad36)") (class "Default")
      (node (ref "IC2") (pin "36") (pinfunction "D-_36") (pintype "bidirectional"))
    )
    (net (code "75") (name "unconnected-(IC2-DAC2{slash}AN48{slash}CVD48{slash}RPC10{slash}PMPA14{slash}PSPCS{slash}RC10-Pad45)") (class "Default")
      (node (ref "IC2") (pin "45") (pinfunction "DAC2/AN48/CVD48/RPC10/PMPA14/PSPCS/RC10_45") (pintype "bidirectional"))
    )
    (net (code "76") (name "unconnected-(IC2-FLT15{slash}RPB4{slash}PMPA8{slash}RB4(-Pad32)") (class "Default")
      (node (ref "IC2") (pin "32") (pinfunction "FLT15/RPB4/PMPA8/RB4(_32") (pintype "bidirectional"))
    )
    (net (code "77") (name "unconnected-(IC2-OA2IN+{slash}AN1{slash}C2IN1+{slash}RPA1{slash}RA1-Pad14)") (class "Default")
      (node (ref "IC2") (pin "14") (pinfunction "OA2IN+/AN1/C2IN1+/RPA1/RA1_14") (pintype "bidirectional"))
    )
    (net (code "78") (name "unconnected-(IC2-OA2OUT{slash}ANO{slash}C2IN4-{slash}C4IN3-{slash}RPA0{slash}RA0-Pad13)") (class "Default")
      (node (ref "IC2") (pin "13") (pinfunction "OA2OUT/ANO/C2IN4-/C4IN3-/RPA0/RA0_13") (pintype "bidirectional"))
    )
    (net (code "79") (name "unconnected-(IC2-OA3IN+{slash}AN8{slash}CVD8{slash}C3IN1+{slash}C3IN3-{slash}RPC2{slash}FLT3{slash}PMPA13{slash}RC2-Pad23)") (class "Default")
      (node (ref "IC2") (pin "23") (pinfunction "OA3IN+/AN8/CVD8/C3IN1+/C3IN3-/RPC2/FLT3/PMPA13/RC2_23") (pintype "bidirectional"))
    )
    (net (code "80") (name "unconnected-(IC2-OA3IN-{slash}AN7{slash}CVD7{slash}C3IN1-{slash}C4IN1-{slash}RPC1{slash}PMPA7{slash}RC1-Pad22)") (class "Default")
      (node (ref "IC2") (pin "22") (pinfunction "OA3IN-/AN7/CVD7/C3IN1-/C4IN1-/RPC1/PMPA7/RC1_22") (pintype "bidirectional"))
    )
    (net (code "81") (name "unconnected-(IC2-OA3OUT{slash}AN6{slash}CVD6{slash}C3IN4-{slash}C4IN1+{slash}C4IN4-{slash}RPC0{slash}RC0-Pad21)") (class "Default")
      (node (ref "IC2") (pin "21") (pinfunction "OA3OUT/AN6/CVD6/C3IN4-/C4IN1+/C4IN4-/RPC0/RC0_21") (pintype "bidirectional"))
    )
    (net (code "82") (name "unconnected-(IC2-PGEC3{slash}OA1OUT{slash}VREF+{slash}AN3{slash}C1IN4-{slash}C4IN2-{slash}RPB1{slash}CTED1{slash}_PMPA6{slash}RB1-Pad16)") (class "Default")
      (node (ref "IC2") (pin "16") (pinfunction "PGEC3/OA1OUT/VREF+/AN3/C1IN4-/C4IN2-/RPB1/CTED1/_PMPA6/RB1_16") (pintype "bidirectional"))
    )
    (net (code "83") (name "unconnected-(IC2-PGED3{slash}VREF-{slash}OA2IN-{slash}AN2{slash}C2IN1-{slash}RPB0{slash}CTED2{slash}RB0-Pad15)") (class "Default")
      (node (ref "IC2") (pin "15") (pinfunction "PGED3/VREF-/OA2IN-/AN2/C2IN1-/RPB0/CTED2/RB0_15") (pintype "bidirectional"))
    )
    (net (code "84") (name "unconnected-(IC2-RD8-Pad42)") (class "Default")
      (node (ref "IC2") (pin "42") (pinfunction "RD8_42") (pintype "bidirectional"))
    )
    (net (code "85") (name "unconnected-(IC2-RPB13{slash}PWM8H{slash}PWM2L{slash}CTPLS{slash}PMPD3{slash}RB13-Pad63)") (class "Default")
      (node (ref "IC2") (pin "63") (pinfunction "RPB13/PWM8H/PWM2L/CTPLS/PMPD3/RB13_63") (pintype "bidirectional"))
    )
    (net (code "86") (name "unconnected-(IC2-RPB14{slash}PWM1H{slash}VBUSON1{slash}PMPD6{slash}RB14-Pad2)") (class "Default")
      (node (ref "IC2") (pin "2") (pinfunction "RPB14/PWM1H/VBUSON1/PMPD6/RB14_2") (pintype "bidirectional"))
    )
    (net (code "87") (name "unconnected-(IC2-SOSCI{slash}RPC13{slash}RC13-Pad47)") (class "Default")
      (node (ref "IC2") (pin "47") (pinfunction "SOSCI/RPC13/RC13_47") (pintype "bidirectional"))
    )
    (net (code "88") (name "unconnected-(IC2-SOSCO{slash}RPB8{slash}RB8-Pad48)") (class "Default")
      (node (ref "IC2") (pin "48") (pinfunction "SOSCO/RPB8/RB8_48") (pintype "bidirectional"))
    )
    (net (code "89") (name "unconnected-(IC2-TDO{slash}PWM4H{slash}PMPD4{slash}RA10-Pad64)") (class "Default")
      (node (ref "IC2") (pin "64") (pinfunction "TDO/PWM4H/PMPD4/RA10_64") (pintype "bidirectional"))
    )
    (net (code "90") (name "unconnected-(IC2-TMS{slash}OA5IN-{slash}AN27{slash}CVD27{slash}C5IN1-{slash}RPB9{slash}RB9-Pad49)") (class "Default")
      (node (ref "IC2") (pin "49") (pinfunction "TMS/OA5IN-/AN27/CVD27/C5IN1-/RPB9/RB9_49") (pintype "bidirectional"))
    )
    (net (code "91") (name "unconnected-(IC2-TRD1{slash}RPC8{slash}PWM5H{slash}PMPWR{slash}PSPWR{slash}RC8-Pad52)") (class "Default")
      (node (ref "IC2") (pin "52") (pinfunction "TRD1/RPC8/PWM5H/PMPWR/PSPWR/RC8_52") (pintype "bidirectional"))
    )
    (net (code "92") (name "unconnected-(IC2-TRD3{slash}RPD6{slash}PWM12L{slash}RD6-Pad54)") (class "Default")
      (node (ref "IC2") (pin "54") (pinfunction "TRD3/RPD6/PWM12L/RD6_54") (pintype "bidirectional"))
    )
    (net (code "93") (name "unconnected-(IC2-VBUS-Pad34)") (class "Default")
      (node (ref "IC2") (pin "34") (pinfunction "VBUS_34") (pintype "bidirectional"))
    )
    (net (code "94") (name "unconnected-(IC3-NC-Pad6)") (class "Default")
      (node (ref "IC3") (pin "6") (pinfunction "NC_6") (pintype "no_connect"))
    )
    (net (code "95") (name "unconnected-(IC3-NC_2-Pad7)") (class "Default")
      (node (ref "IC3") (pin "7") (pinfunction "NC_2_7") (pintype "no_connect"))
    )
    (net (code "96") (name "unconnected-(IC5-NC-Pad6)") (class "Default")
      (node (ref "IC5") (pin "6") (pinfunction "NC_6") (pintype "no_connect"))
    )
    (net (code "97") (name "unconnected-(IC5-NC_2-Pad7)") (class "Default")
      (node (ref "IC5") (pin "7") (pinfunction "NC_2_7") (pintype "no_connect"))
    )
    (net (code "98") (name "unconnected-(J1-Pad3)") (class "Default")
      (node (ref "J1") (pin "3") (pinfunction "3_3") (pintype "passive"))
    )
    (net (code "99") (name "unconnected-(J1-Pad4)") (class "Default")
      (node (ref "J1") (pin "4") (pinfunction "4_4") (pintype "passive"))
    )
    (net (code "100") (name "unconnected-(U$1-RX-PadJ1-1)") (class "Default")
      (node (ref "U$1") (pin "J1-1") (pinfunction "RX_J1-1") (pintype "bidirectional"))
    )
    (net (code "101") (name "unconnected-(U$1-SDO-PadJ2-2)") (class "Default")
      (node (ref "U$1") (pin "J2-2") (pinfunction "SDO_J2-2") (pintype "bidirectional"))
    )
    (net (code "102") (name "~{DAC_CS}") (class "Default")
      (node (ref "IC2") (pin "33") (pinfunction "OA5IN+/DAC1/AN24/CVD24/C5IN1+/C5IN3-/RPA4/T1CK/T1G/_RA4_33") (pintype "bidirectional"))
      (node (ref "U4") (pin "15") (pinfunction "ML_15") (pintype "input"))
    )
    (net (code "103") (name "~{MCLR}") (class "Default")
      (node (ref "CN1") (pin "1") (pinfunction "1_1") (pintype "passive"))
      (node (ref "IC2") (pin "7") (pinfunction "~{MCLR}_7") (pintype "bidirectional"))
      (node (ref "R1") (pin "2") (pinfunction "2_2") (pintype "passive"))
    )
  )
)
